# circuitPendulum4TIA01_screenShot.net
KiCad netlist of a schematic drawn in EAGLE
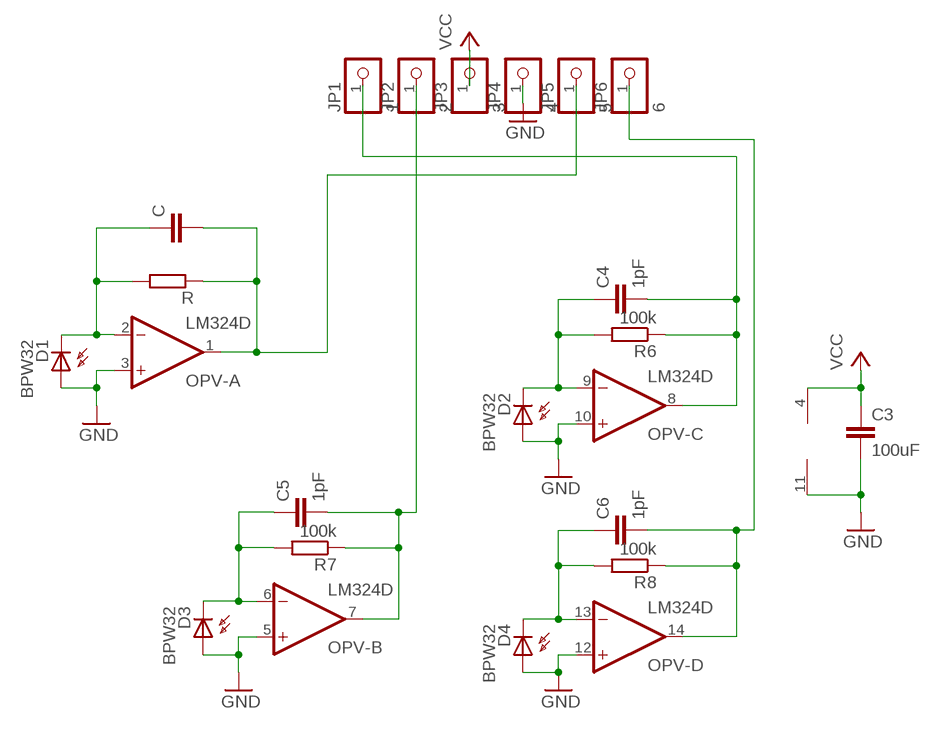
[diagram p0: schematic, sheet 1]

(export (version "E")
  (design (tool "Eeschema 10.0.6"))
  (components
    (comp (ref "C")
      (value "C-EUC0603")
      (footprint "eagle-import:C0603")
      (libsource (lib "eagle-import") (part "C-EUC0603"))
    )
    (comp (ref "C3")
      (value "100uF")
      (footprint "eagle-import:C0603")
      (libsource (lib "eagle-import") (part "C-EUC0603"))
    )
    (comp (ref "C4")
      (value "1pF")
      (footprint "eagle-import:C0603")
      (libsource (lib "eagle-import") (part "C-EUC0603"))
    )
    (comp (ref "C5")
      (value "1pF")
      (footprint "eagle-import:C0603")
      (libsource (lib "eagle-import") (part "C-EUC0603"))
    )
    (comp (ref "C6")
      (value "1pF")
      (footprint "eagle-import:C0603")
      (libsource (lib "eagle-import") (part "C-EUC0603"))
    )
    (comp (ref "D1")
      (value "BPW32")
      (footprint "eagle-import:BPW32")
      (libsource (lib "eagle-import") (part "BPW32"))
    )
    (comp (ref "D2")
      (value "BPW32")
      (footprint "eagle-import:BPW32")
      (libsource (lib "eagle-import") (part "BPW32"))
    )
    (comp (ref "D3")
      (value "BPW32")
      (footprint "eagle-import:BPW32")
      (libsource (lib "eagle-import") (part "BPW32"))
    )
    (comp (ref "D4")
      (value "BPW32")
      (footprint "eagle-import:BPW32")
      (libsource (lib "eagle-import") (part "BPW32"))
    )
    (comp (ref "JP1")
      (value "1")
      (footprint "eagle-import:1X01SMD")
      (libsource (lib "eagle-import") (part "PINHD-1X1_2.54-SMD"))
    )
    (comp (ref "JP2")
      (value "2")
      (footprint "eagle-import:1X01SMD")
      (libsource (lib "eagle-import") (part "PINHD-1X1_2.54-SMD"))
    )
    (comp (ref "JP3")
      (value "3")
      (footprint "eagle-import:1X01SMD")
      (libsource (lib "eagle-import") (part "PINHD-1X1_2.54-SMD"))
    )
    (comp (ref "JP4")
      (value "4")
      (footprint "eagle-import:1X01SMD")
      (libsource (lib "eagle-import") (part "PINHD-1X1_2.54-SMD"))
    )
    (comp (ref "JP5")
      (value "5")
      (footprint "eagle-import:1X01SMD")
      (libsource (lib "eagle-import") (part "PINHD-1X1_2.54-SMD"))
    )
    (comp (ref "JP6")
      (value "6")
      (footprint "eagle-import:1X01SMD")
      (libsource (lib "eagle-import") (part "PINHD-1X1_2.54-SMD"))
    )
    (comp (ref "OPV-")
      (value "LM324D")
      (footprint "eagle-import:SO14")
      (libsource (lib "eagle-import") (part "LM324D"))
    )
    (comp (ref "R")
      (value "R-EU_R0603")
      (footprint "eagle-import:R0603")
      (libsource (lib "eagle-import") (part "R-EU_R0603"))
    )
    (comp (ref "R6")
      (value "100k")
      (footprint "eagle-import:R0603")
      (libsource (lib "eagle-import") (part "R-EU_R0603"))
    )
    (comp (ref "R7")
      (value "100k")
      (footprint "eagle-import:R0603")
      (libsource (lib "eagle-import") (part "R-EU_R0603"))
    )
    (comp (ref "R8")
      (value "100k")
      (footprint "eagle-import:R0603")
      (libsource (lib "eagle-import") (part "R-EU_R0603"))
    )
  )
  (nets
    (net (code "1") (name "GND") (class "Default")
      (node (ref "C3") (pin "2") (pinfunction "2_2") (pintype "passive"))
      (node (ref "D1") (pin "A") (pinfunction "A_A") (pintype "passive"))
      (node (ref "D2") (pin "A") (pinfunction "A_A") (pintype "passive"))
      (node (ref "D3") (pin "A") (pinfunction "A_A") (pintype "passive"))
      (node (ref "D4") (pin "A") (pinfunction "A_A") (pintype "passive"))
      (node (ref "JP4") (pin "1") (pinfunction "1_1") (pintype "passive"))
      (node (ref "OPV-") (pin "10") (pinfunction "+IN_10") (pintype "input"))
      (node (ref "OPV-") (pin "11") (pinfunction "V-_11") (pintype "power_in"))
      (node (ref "OPV-") (pin "12") (pinfunction "+IN_12") (pintype "input"))
      (node (ref "OPV-") (pin "3") (pinfunction "+IN_3") (pintype "input"))
      (node (ref "OPV-") (pin "5") (pinfunction "+IN_5") (pintype "input"))
    )
    (net (code "2") (name "Net-(D1-C)") (class "Default")
      (node (ref "C") (pin "1") (pinfunction "1_1") (pintype "passive"))
      (node (ref "D1") (pin "K") (pinfunction "C_K") (pintype "passive"))
      (node (ref "OPV-") (pin "2") (pinfunction "-IN_2") (pintype "input"))
      (node (ref "R") (pin "2") (pinfunction "2_2") (pintype "passive"))
    )
    (net (code "3") (name "Net-(D2-C)") (class "Default")
      (node (ref "C4") (pin "1") (pinfunction "1_1") (pintype "passive"))
      (node (ref "D2") (pin "K") (pinfunction "C_K") (pintype "passive"))
      (node (ref "OPV-") (pin "9") (pinfunction "-IN_9") (pintype "input"))
      (node (ref "R6") (pin "2") (pinfunction "2_2") (pintype "passive"))
    )
    (net (code "4") (name "Net-(D3-C)") (class "Default")
      (node (ref "C5") (pin "1") (pinfunction "1_1") (pintype "passive"))
      (node (ref "D3") (pin "K") (pinfunction "C_K") (pintype "passive"))
      (node (ref "OPV-") (pin "6") (pinfunction "-IN_6") (pintype "input"))
      (node (ref "R7") (pin "2") (pinfunction "2_2") (pintype "passive"))
    )
    (net (code "5") (name "Net-(D4-C)") (class "Default")
      (node (ref "C6") (pin "1") (pinfunction "1_1") (pintype "passive"))
      (node (ref "D4") (pin "K") (pinfunction "C_K") (pintype "passive"))
      (node (ref "OPV-") (pin "13") (pinfunction "-IN_13") (pintype "input"))
      (node (ref "R8") (pin "2") (pinfunction "2_2") (pintype "passive"))
    )
    (net (code "6") (name "Net-(OPV-A-OUT)") (class "Default")
      (node (ref "C") (pin "2") (pinfunction "2_2") (pintype "passive"))
      (node (ref "JP5") (pin "1") (pinfunction "1_1") (pintype "passive"))
      (node (ref "OPV-") (pin "1") (pinfunction "OUT_1") (pintype "output"))
      (node (ref "R") (pin "1") (pinfunction "1_1") (pintype "passive"))
    )
    (net (code "7") (name "Net-(OPV-B-OUT)") (class "Default")
      (node (ref "C5") (pin "2") (pinfunction "2_2") (pintype "passive"))
      (node (ref "JP2") (pin "1") (pinfunction "1_1") (pintype "passive"))
      (node (ref "OPV-") (pin "7") (pinfunction "OUT_7") (pintype "output"))
      (node (ref "R7") (pin "1") (pinfunction "1_1") (pintype "passive"))
    )
    (net (code "8") (name "Net-(OPV-C-OUT)") (class "Default")
      (node (ref "C4") (pin "2") (pinfunction "2_2") (pintype "passive"))
      (node (ref "JP1") (pin "1") (pinfunction "1_1") (pintype "passive"))
      (node (ref "OPV-") (pin "8") (pinfunction "OUT_8") (pintype "output"))
      (node (ref "R6") (pin "1") (pinfunction "1_1") (pintype "passive"))
    )
    (net (code "9") (name "Net-(OPV-D-OUT)") (class "Default")
      (node (ref "C6") (pin "2") (pinfunction "2_2") (pintype "passive"))
      (node (ref "JP6") (pin "1") (pinfunction "1_1") (pintype "passive"))
      (node (ref "OPV-") (pin "14") (pinfunction "OUT_14") (pintype "output"))
      (node (ref "R8") (pin "1") (pinfunction "1_1") (pintype "passive"))
    )
    (net (code "10") (name "VCC") (class "Default")
      (node (ref "C3") (pin "1") (pinfunction "1_1") (pintype "passive"))
      (node (ref "JP3") (pin "1") (pinfunction "1_1") (pintype "passive"))
      (node (ref "OPV-") (pin "4") (pinfunction "V+_4") (pintype "power_in"))
    )
  )
)
